# WlPK1_main.net
KiCad netlist of a schematic drawn in Altium Designer
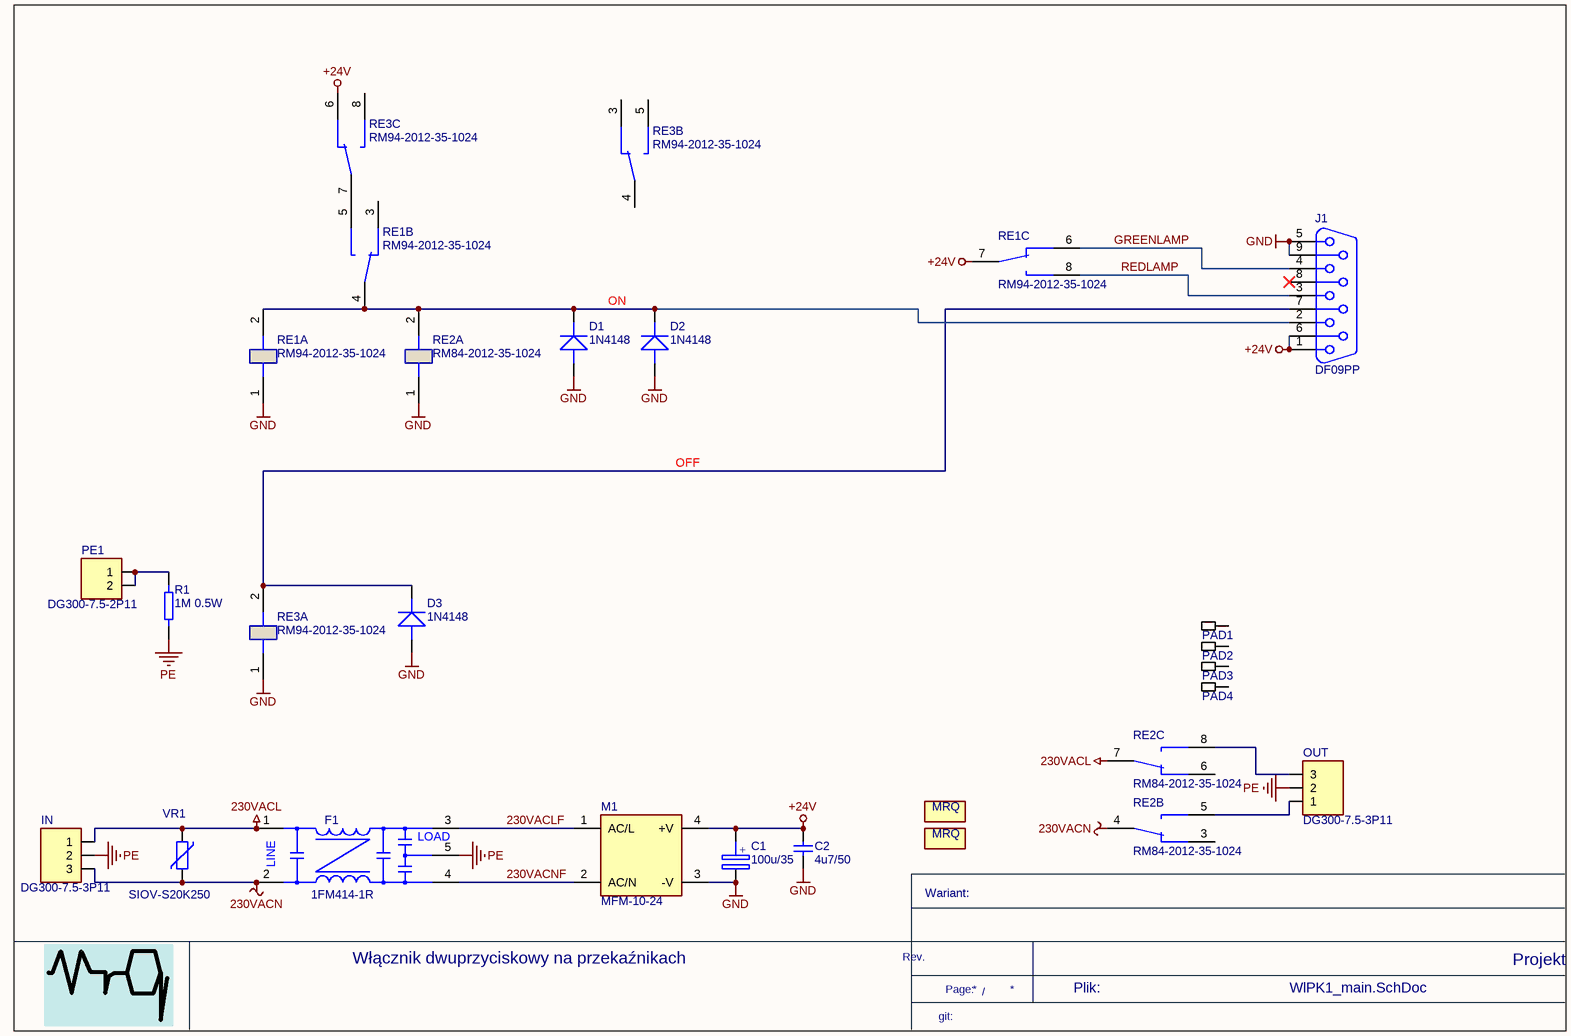
[diagram p0: WlPK1_main.SchDoc]

(export (version "E")
  (design (tool "Eeschema 10.0.6"))
  (components
    (comp (ref "C1") (value "100u/35") (footprint "CE1028") (libsource (lib "PartsMySQL") (part "CEL")))
    (comp (ref "C2") (value "4u7/50") (footprint "1210") (libsource (lib "PartsMySQL") (part "C")))
    (comp (ref "D1") (value "1N4148") (footprint "CE02") (libsource (lib "PartsMySQL") (part "DIODE")))
    (comp (ref "D2") (value "1N4148") (footprint "CE02") (libsource (lib "PartsMySQL") (part "DIODE")))
    (comp (ref "D3") (value "1N4148") (footprint "CE02") (libsource (lib "PartsMySQL") (part "DIODE")))
    (comp (ref "F1") (value "1FM414-1R") (footprint "1FM414") (libsource (lib "PartsMySQL") (part "1FM414")))
    (comp (ref "IN")
      (value "DG300-7.5-3P11")
      (footprint "DG300-7.5-3P11")
      (libsource (lib "PartsMySQL") (part "HEADER3"))
    )
    (comp (ref "J1") (value "DF09PP") (footprint "DB9/F") (libsource (lib "PartsMySQL") (part "DB9")))
    (comp (ref "LOGO1")
      (value "MRQ_5")
      (footprint "MRQ_5_TL")
      (libsource (lib "PartsMySQL") (part "MRQLOGO"))
    )
    (comp (ref "LOGO2")
      (value "MRQ_5")
      (footprint "MRQ_5_TL")
      (libsource (lib "PartsMySQL") (part "MRQLOGO"))
    )
    (comp (ref "M1")
      (value "MFM-10-24")
      (footprint "MFM-10-24")
      (libsource (lib "PartsMySQL") (part "PM-10-5"))
    )
    (comp (ref "OUT")
      (value "DG300-7.5-3P11")
      (footprint "DG300-7.5-3P11")
      (libsource (lib "") (part "HEADER3_1"))
    )
    (comp (ref "PAD1")
      (value "PAD3_5MM")
      (footprint "PAD3_5MM")
      (libsource (lib "PartsMySQL") (part "CLAMP_NOBOM"))
    )
    (comp (ref "PAD2")
      (value "PAD3_5MM")
      (footprint "PAD3_5MM")
      (libsource (lib "PartsMySQL") (part "CLAMP_NOBOM"))
    )
    (comp (ref "PAD3")
      (value "PAD3_5MM")
      (footprint "PAD3_5MM")
      (libsource (lib "PartsMySQL") (part "CLAMP_NOBOM"))
    )
    (comp (ref "PAD4")
      (value "PAD3_5MM")
      (footprint "PAD3_5MM")
      (libsource (lib "PartsMySQL") (part "CLAMP_NOBOM"))
    )
    (comp (ref "PE1")
      (value "DG300-7.5-2P11")
      (footprint "DG300-7.5-2P11")
      (libsource (lib "PartsMySQL") (part "HEADER2"))
    )
    (comp (ref "R1") (value "1M 0.5W") (footprint "R502816") (libsource (lib "PartsMySQL") (part "R")))
    (comp (ref "RE1")
      (value "RM94-2012-35-1024")
      (footprint "RM84-P")
      (libsource (lib "PartsMySQL") (part "RM84-P"))
    )
    (comp (ref "RE2")
      (value "RM84-2012-35-1024")
      (footprint "RM84-P")
      (libsource (lib "PartsMySQL") (part "RM84-P"))
    )
    (comp (ref "RE3")
      (value "RM94-2012-35-1024")
      (footprint "RM84-P")
      (libsource (lib "PartsMySQL") (part "RM84-P"))
    )
    (comp (ref "VR1")
      (value "SIOV-S20K250")
      (footprint "SIOV-S20K275")
      (libsource (lib "PartsMySQL") (part "VARISTOR"))
    )
  )
  (nets
    (net (code "1") (name "+24V") (class "Default")
      (node (ref "C1") (pin "2") (pinfunction "2_2") (pintype "passive"))
      (node (ref "C2") (pin "1") (pinfunction "1_1") (pintype "passive"))
      (node (ref "J1") (pin "1") (pinfunction "1_1") (pintype "passive"))
      (node (ref "J1") (pin "6") (pinfunction "6_6") (pintype "passive"))
      (node (ref "M1") (pin "4") (pinfunction "+V_4") (pintype "passive"))
      (node (ref "RE1") (pin "7") (pinfunction "11_7") (pintype "passive"))
      (node (ref "RE3") (pin "6") (pinfunction "12_6") (pintype "passive"))
    )
    (net (code "2") (name "/230VACLF") (class "Default")
      (node (ref "F1") (pin "3") (pinfunction "OUT2_3") (pintype "passive"))
      (node (ref "M1") (pin "1") (pinfunction "AC/L_1") (pintype "passive"))
    )
    (net (code "3") (name "/230VACNF") (class "Default")
      (node (ref "F1") (pin "4") (pinfunction "OUT1_4") (pintype "passive"))
      (node (ref "M1") (pin "2") (pinfunction "AC/N_2") (pintype "passive"))
    )
    (net (code "4") (name "/GREENLAMP") (class "Default")
      (node (ref "J1") (pin "4") (pinfunction "4_4") (pintype "passive"))
      (node (ref "RE1") (pin "6") (pinfunction "12_6") (pintype "passive"))
    )
    (net (code "5") (name "/OFF") (class "Default")
      (node (ref "D3") (pin "CATH") (pinfunction "CATH_CATH") (pintype "passive"))
      (node (ref "J1") (pin "7") (pinfunction "7_7") (pintype "passive"))
      (node (ref "RE3") (pin "2") (pinfunction "A2_2") (pintype "passive"))
    )
    (net (code "6") (name "/ON") (class "Default")
      (node (ref "D1") (pin "CATH") (pinfunction "CATH_CATH") (pintype "passive"))
      (node (ref "D2") (pin "CATH") (pinfunction "CATH_CATH") (pintype "passive"))
      (node (ref "J1") (pin "2") (pinfunction "2_2") (pintype "passive"))
      (node (ref "RE1") (pin "2") (pinfunction "A2_2") (pintype "passive"))
      (node (ref "RE1") (pin "4") (pinfunction "21_4") (pintype "passive"))
      (node (ref "RE2") (pin "2") (pinfunction "A2_2") (pintype "passive"))
    )
    (net (code "7") (name "/REDLAMP") (class "Default")
      (node (ref "J1") (pin "3") (pinfunction "3_3") (pintype "passive"))
      (node (ref "RE1") (pin "8") (pinfunction "14_8") (pintype "passive"))
    )
    (net (code "8") (name "230VACL") (class "Default")
      (node (ref "F1") (pin "1") (pinfunction "IN1_1") (pintype "passive"))
      (node (ref "IN") (pin "1") (pinfunction "1_1") (pintype "passive"))
      (node (ref "RE2") (pin "7") (pinfunction "11_7") (pintype "passive"))
      (node (ref "VR1") (pin "1") (pinfunction "1_1") (pintype "passive"))
    )
    (net (code "9") (name "230VACN") (class "Default")
      (node (ref "F1") (pin "2") (pinfunction "IN2_2") (pintype "passive"))
      (node (ref "IN") (pin "3") (pinfunction "3_3") (pintype "passive"))
      (node (ref "RE2") (pin "4") (pinfunction "21_4") (pintype "passive"))
      (node (ref "VR1") (pin "2") (pinfunction "2_2") (pintype "passive"))
    )
    (net (code "10") (name "GND") (class "Default")
      (node (ref "C1") (pin "1") (pinfunction "1_1") (pintype "passive"))
      (node (ref "C2") (pin "2") (pinfunction "2_2") (pintype "passive"))
      (node (ref "D1") (pin "ANOD") (pinfunction "ANOD_ANOD") (pintype "passive"))
      (node (ref "D2") (pin "ANOD") (pinfunction "ANOD_ANOD") (pintype "passive"))
      (node (ref "D3") (pin "ANOD") (pinfunction "ANOD_ANOD") (pintype "passive"))
      (node (ref "J1") (pin "5") (pinfunction "5_5") (pintype "passive"))
      (node (ref "J1") (pin "9") (pinfunction "9_9") (pintype "passive"))
      (node (ref "M1") (pin "3") (pinfunction "-V_3") (pintype "passive"))
      (node (ref "RE1") (pin "1") (pinfunction "A1_1") (pintype "passive"))
      (node (ref "RE2") (pin "1") (pinfunction "A1_1") (pintype "passive"))
      (node (ref "RE3") (pin "1") (pinfunction "A1_1") (pintype "passive"))
    )
    (net (code "11") (name "Net-(PE1-Pad1)") (class "Default")
      (node (ref "PE1") (pin "1") (pinfunction "1_1") (pintype "passive"))
      (node (ref "PE1") (pin "2") (pinfunction "2_2") (pintype "passive"))
      (node (ref "R1") (pin "2") (pinfunction "2_2") (pintype "passive"))
    )
    (net (code "12") (name "Net-(RE1B-24)") (class "Default")
      (node (ref "RE1") (pin "5") (pinfunction "24_5") (pintype "passive"))
      (node (ref "RE3") (pin "7") (pinfunction "11_7") (pintype "passive"))
    )
    (net (code "13") (name "Net-(RE2B-24)") (class "Default")
      (node (ref "OUT") (pin "1") (pinfunction "1_1") (pintype "passive"))
      (node (ref "RE2") (pin "5") (pinfunction "24_5") (pintype "passive"))
    )
    (net (code "14") (name "Net-(RE2C-14)") (class "Default")
      (node (ref "OUT") (pin "3") (pinfunction "3_3") (pintype "passive"))
      (node (ref "RE2") (pin "8") (pinfunction "14_8") (pintype "passive"))
    )
    (net (code "15") (name "PE") (class "Default")
      (node (ref "F1") (pin "5") (pinfunction "5_5") (pintype "passive"))
      (node (ref "IN") (pin "2") (pinfunction "2_2") (pintype "passive"))
      (node (ref "OUT") (pin "2") (pinfunction "2_2") (pintype "passive"))
      (node (ref "R1") (pin "1") (pinfunction "1_1") (pintype "passive"))
    )
    (net (code "16") (name "unconnected-(J1-Pad8)") (class "Default")
      (node (ref "J1") (pin "8") (pinfunction "8_8") (pintype "passive+no_connect"))
    )
    (net (code "17") (name "unconnected-(PAD1-Pad1)") (class "Default")
      (node (ref "PAD1") (pin "1") (pinfunction "1_1") (pintype "passive"))
    )
    (net (code "18") (name "unconnected-(PAD2-Pad1)") (class "Default")
      (node (ref "PAD2") (pin "1") (pinfunction "1_1") (pintype "passive"))
    )
    (net (code "19") (name "unconnected-(PAD3-Pad1)") (class "Default")
      (node (ref "PAD3") (pin "1") (pinfunction "1_1") (pintype "passive"))
    )
    (net (code "20") (name "unconnected-(PAD4-Pad1)") (class "Default")
      (node (ref "PAD4") (pin "1") (pinfunction "1_1") (pintype "passive"))
    )
    (net (code "21") (name "unconnected-(RE1B-22-Pad3)") (class "Default")
      (node (ref "RE1") (pin "3") (pinfunction "22_3") (pintype "passive"))
    )
    (net (code "22") (name "unconnected-(RE2B-22-Pad3)") (class "Default")
      (node (ref "RE2") (pin "3") (pinfunction "22_3") (pintype "passive"))
    )
    (net (code "23") (name "unconnected-(RE2C-12-Pad6)") (class "Default")
      (node (ref "RE2") (pin "6") (pinfunction "12_6") (pintype "passive"))
    )
    (net (code "24") (name "unconnected-(RE3B-21-Pad4)") (class "Default")
      (node (ref "RE3") (pin "4") (pinfunction "21_4") (pintype "passive"))
    )
    (net (code "25") (name "unconnected-(RE3B-22-Pad3)") (class "Default")
      (node (ref "RE3") (pin "3") (pinfunction "22_3") (pintype "passive"))
    )
    (net (code "26") (name "unconnected-(RE3B-24-Pad5)") (class "Default")
      (node (ref "RE3") (pin "5") (pinfunction "24_5") (pintype "passive"))
    )
    (net (code "27") (name "unconnected-(RE3C-14-Pad8)") (class "Default")
      (node (ref "RE3") (pin "8") (pinfunction "14_8") (pintype "passive"))
    )
  )
)
